# NixieModule_IN12.net
KiCad netlist of a schematic drawn in EAGLE
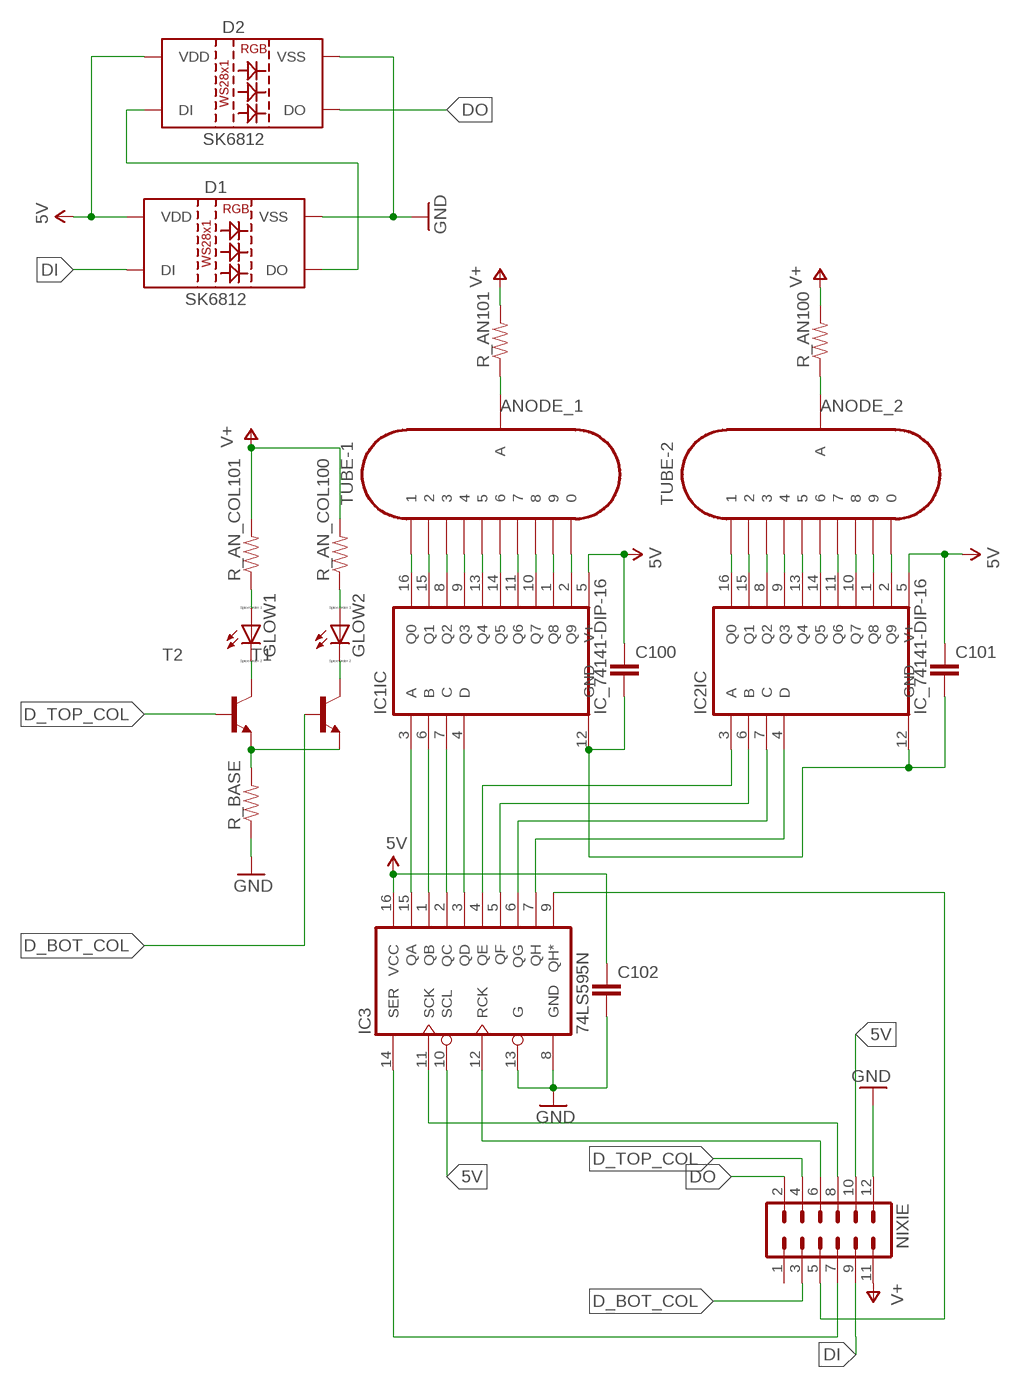
[diagram p0: schematic, sheet 1]

(export (version "E")
  (design (tool "Eeschema 10.0.6"))
  (components
    (comp (ref "C100")
      (value "C-EU050-024X044")
      (footprint "eagle-import:C050-024X044")
      (libsource (lib "eagle-import") (part "C-EU050-024X044"))
    )
    (comp (ref "C101")
      (value "C-EU050-024X044")
      (footprint "eagle-import:C050-024X044")
      (libsource (lib "eagle-import") (part "C-EU050-024X044"))
    )
    (comp (ref "C102")
      (value "C-EU050-024X044")
      (footprint "eagle-import:C050-024X044")
      (libsource (lib "eagle-import") (part "C-EU050-024X044"))
    )
    (comp (ref "D1")
      (value "SK6812")
      (footprint "eagle-import:WS2812B")
      (libsource (lib "eagle-import") (part "WS2812B"))
    )
    (comp (ref "D2")
      (value "SK6812")
      (footprint "eagle-import:WS2812B")
      (libsource (lib "eagle-import") (part "WS2812B"))
    )
    (comp (ref "GLOW1")
      (value "LED_ELD260")
      (footprint "eagle-import:LED_LD260")
      (libsource (lib "eagle-import") (part "LED_ELD260"))
    )
    (comp (ref "GLOW2")
      (value "LED_ELD260")
      (footprint "eagle-import:LED_LD260")
      (libsource (lib "eagle-import") (part "LED_ELD260"))
    )
    (comp (ref "IC1")
      (value "IC_74141-DIP-16")
      (footprint "eagle-import:DIL16")
      (libsource (lib "eagle-import") (part "IC_74141-DIP-16"))
    )
    (comp (ref "IC2")
      (value "IC_74141-DIP-16")
      (footprint "eagle-import:DIL16")
      (libsource (lib "eagle-import") (part "IC_74141-DIP-16"))
    )
    (comp (ref "IC3")
      (value "74LS595N")
      (footprint "eagle-import:DIL16")
      (libsource (lib "eagle-import") (part "74595NLS"))
    )
    (comp (ref "NIXIE")
      (value "MA06-2")
      (footprint "eagle-import:MA06-2")
      (libsource (lib "eagle-import") (part "MA06-2"))
    )
    (comp (ref "R_AN100")
      (value "RESISTORPTH-1/4W")
      (footprint "eagle-import:AXIAL-0.4")
      (libsource (lib "eagle-import") (part "RESISTORPTH-1/4W"))
    )
    (comp (ref "R_AN101")
      (value "RESISTORPTH-1/4W")
      (footprint "eagle-import:AXIAL-0.4")
      (libsource (lib "eagle-import") (part "RESISTORPTH-1/4W"))
    )
    (comp (ref "R_AN_COL100")
      (value "RESISTORPTH-1/4W")
      (footprint "eagle-import:AXIAL-0.4")
      (libsource (lib "eagle-import") (part "RESISTORPTH-1/4W"))
    )
    (comp (ref "R_AN_COL101")
      (value "RESISTORPTH-1/4W")
      (footprint "eagle-import:AXIAL-0.4")
      (libsource (lib "eagle-import") (part "RESISTORPTH-1/4W"))
    )
    (comp (ref "R_BASE")
      (value "RESISTORPTH-1/4W")
      (footprint "eagle-import:AXIAL-0.4")
      (libsource (lib "eagle-import") (part "RESISTORPTH-1/4W"))
    )
    (comp (ref "T1")
      (value "-NPN-TO92-EBC")
      (footprint "eagle-import:TO92-EBC")
      (libsource (lib "eagle-import") (part "-NPN-TO92-EBC"))
    )
    (comp (ref "T2")
      (value "-NPN-TO92-EBC")
      (footprint "eagle-import:TO92-EBC")
      (libsource (lib "eagle-import") (part "-NPN-TO92-EBC"))
    )
    (comp (ref "TUBE-1")
      (value "IN-12A")
      (footprint "eagle-import:IN-12")
      (libsource (lib "eagle-import") (part "IN-12A"))
    )
    (comp (ref "TUBE-2")
      (value "IN-12A")
      (footprint "eagle-import:IN-12")
      (libsource (lib "eagle-import") (part "IN-12A"))
    )
  )
  (nets
    (net (code "1") (name "/ANODE_1") (class "Default")
      (node (ref "R_AN101") (pin "P$1") (pinfunction "1_P$1") (pintype "passive"))
      (node (ref "TUBE-1") (pin "A") (pinfunction "A_A") (pintype "bidirectional"))
    )
    (net (code "2") (name "/ANODE_2") (class "Default")
      (node (ref "R_AN100") (pin "P$1") (pinfunction "1_P$1") (pintype "passive"))
      (node (ref "TUBE-2") (pin "A") (pinfunction "A_A") (pintype "bidirectional"))
    )
    (net (code "3") (name "5V") (class "Default")
      (node (ref "C100") (pin "1") (pinfunction "1_1") (pintype "passive"))
      (node (ref "C101") (pin "1") (pinfunction "1_1") (pintype "passive"))
      (node (ref "C102") (pin "1") (pinfunction "1_1") (pintype "passive"))
      (node (ref "D1") (pin "1") (pinfunction "VDD_1") (pintype "bidirectional"))
      (node (ref "D2") (pin "1") (pinfunction "VDD_1") (pintype "bidirectional"))
      (node (ref "IC1") (pin "5") (pinfunction "V+_5") (pintype "power_in"))
      (node (ref "IC2") (pin "5") (pinfunction "V+_5") (pintype "power_in"))
      (node (ref "IC3") (pin "10") (pinfunction "SCL_10") (pintype "input"))
      (node (ref "IC3") (pin "16") (pinfunction "VCC_16") (pintype "power_in"))
      (node (ref "NIXIE") (pin "10") (pinfunction "10_10") (pintype "passive"))
    )
    (net (code "4") (name "DI") (class "Default")
      (node (ref "D1") (pin "4") (pinfunction "DI_4") (pintype "bidirectional"))
      (node (ref "NIXIE") (pin "9") (pinfunction "9_9") (pintype "passive"))
    )
    (net (code "5") (name "DO") (class "Default")
      (node (ref "D2") (pin "2") (pinfunction "DO_2") (pintype "bidirectional"))
      (node (ref "NIXIE") (pin "2") (pinfunction "2_2") (pintype "passive"))
    )
    (net (code "6") (name "D_BOT_COL") (class "Default")
      (node (ref "NIXIE") (pin "3") (pinfunction "3_3") (pintype "passive"))
      (node (ref "T1") (pin "B") (pinfunction "B_B") (pintype "passive"))
    )
    (net (code "7") (name "D_TOP_COL") (class "Default")
      (node (ref "NIXIE") (pin "4") (pinfunction "4_4") (pintype "passive"))
      (node (ref "T2") (pin "B") (pinfunction "B_B") (pintype "passive"))
    )
    (net (code "8") (name "GND") (class "Default")
      (node (ref "C100") (pin "2") (pinfunction "2_2") (pintype "passive"))
      (node (ref "C101") (pin "2") (pinfunction "2_2") (pintype "passive"))
      (node (ref "C102") (pin "2") (pinfunction "2_2") (pintype "passive"))
      (node (ref "D1") (pin "3") (pinfunction "VSS_3") (pintype "bidirectional"))
      (node (ref "D2") (pin "3") (pinfunction "VSS_3") (pintype "bidirectional"))
      (node (ref "IC1") (pin "12") (pinfunction "GND_12") (pintype "power_in"))
      (node (ref "IC2") (pin "12") (pinfunction "GND_12") (pintype "power_in"))
      (node (ref "IC3") (pin "13") (pinfunction "G_13") (pintype "input"))
      (node (ref "IC3") (pin "8") (pinfunction "GND_8") (pintype "power_in"))
      (node (ref "NIXIE") (pin "12") (pinfunction "12_12") (pintype "passive"))
      (node (ref "R_BASE") (pin "P$1") (pinfunction "1_P$1") (pintype "passive"))
    )
    (net (code "9") (name "Net-(D1-DO)") (class "Default")
      (node (ref "D1") (pin "2") (pinfunction "DO_2") (pintype "bidirectional"))
      (node (ref "D2") (pin "4") (pinfunction "DI_4") (pintype "bidirectional"))
    )
    (net (code "10") (name "Net-(GLOW1-C)") (class "Default")
      (node (ref "GLOW1") (pin "K") (pinfunction "C_K") (pintype "passive"))
      (node (ref "T2") (pin "C") (pinfunction "C_C") (pintype "passive"))
    )
    (net (code "11") (name "Net-(GLOW2-C)") (class "Default")
      (node (ref "GLOW2") (pin "K") (pinfunction "C_K") (pintype "passive"))
      (node (ref "T1") (pin "C") (pinfunction "C_C") (pintype "passive"))
    )
    (net (code "12") (name "Net-(IC1A-A)") (class "Default")
      (node (ref "IC1") (pin "3") (pinfunction "A_3") (pintype "input"))
      (node (ref "IC3") (pin "15") (pinfunction "QA_15") (pintype "tri_state"))
    )
    (net (code "13") (name "Net-(IC1A-B)") (class "Default")
      (node (ref "IC1") (pin "6") (pinfunction "B_6") (pintype "input"))
      (node (ref "IC3") (pin "1") (pinfunction "QB_1") (pintype "tri_state"))
    )
    (net (code "14") (name "Net-(IC1A-C)") (class "Default")
      (node (ref "IC1") (pin "7") (pinfunction "C_7") (pintype "input"))
      (node (ref "IC3") (pin "2") (pinfunction "QC_2") (pintype "tri_state"))
    )
    (net (code "15") (name "Net-(IC1A-D)") (class "Default")
      (node (ref "IC1") (pin "4") (pinfunction "D_4") (pintype "input"))
      (node (ref "IC3") (pin "3") (pinfunction "QD_3") (pintype "tri_state"))
    )
    (net (code "16") (name "Net-(IC1A-Q0)") (class "Default")
      (node (ref "IC1") (pin "16") (pinfunction "Q0_16") (pintype "output"))
      (node (ref "TUBE-1") (pin "1") (pinfunction "1_1") (pintype "bidirectional"))
    )
    (net (code "17") (name "Net-(IC1A-Q1)") (class "Default")
      (node (ref "IC1") (pin "15") (pinfunction "Q1_15") (pintype "output"))
      (node (ref "TUBE-1") (pin "2") (pinfunction "2_2") (pintype "bidirectional"))
    )
    (net (code "18") (name "Net-(IC1A-Q2)") (class "Default")
      (node (ref "IC1") (pin "8") (pinfunction "Q2_8") (pintype "output"))
      (node (ref "TUBE-1") (pin "3") (pinfunction "3_3") (pintype "bidirectional"))
    )
    (net (code "19") (name "Net-(IC1A-Q3)") (class "Default")
      (node (ref "IC1") (pin "9") (pinfunction "Q3_9") (pintype "output"))
      (node (ref "TUBE-1") (pin "4") (pinfunction "4_4") (pintype "bidirectional"))
    )
    (net (code "20") (name "Net-(IC1A-Q4)") (class "Default")
      (node (ref "IC1") (pin "13") (pinfunction "Q4_13") (pintype "output"))
      (node (ref "TUBE-1") (pin "5") (pinfunction "5_5") (pintype "bidirectional"))
    )
    (net (code "21") (name "Net-(IC1A-Q5)") (class "Default")
      (node (ref "IC1") (pin "14") (pinfunction "Q5_14") (pintype "output"))
      (node (ref "TUBE-1") (pin "6") (pinfunction "6_6") (pintype "bidirectional"))
    )
    (net (code "22") (name "Net-(IC1A-Q6)") (class "Default")
      (node (ref "IC1") (pin "11") (pinfunction "Q6_11") (pintype "output"))
      (node (ref "TUBE-1") (pin "7") (pinfunction "7_7") (pintype "bidirectional"))
    )
    (net (code "23") (name "Net-(IC1A-Q7)") (class "Default")
      (node (ref "IC1") (pin "10") (pinfunction "Q7_10") (pintype "output"))
      (node (ref "TUBE-1") (pin "8") (pinfunction "8_8") (pintype "bidirectional"))
    )
    (net (code "24") (name "Net-(IC1A-Q8)") (class "Default")
      (node (ref "IC1") (pin "1") (pinfunction "Q8_1") (pintype "output"))
      (node (ref "TUBE-1") (pin "9") (pinfunction "9_9") (pintype "bidirectional"))
    )
    (net (code "25") (name "Net-(IC1A-Q9)") (class "Default")
      (node (ref "IC1") (pin "2") (pinfunction "Q9_2") (pintype "output"))
      (node (ref "TUBE-1") (pin "0") (pinfunction "0_0") (pintype "bidirectional"))
    )
    (net (code "26") (name "Net-(IC2A-A)") (class "Default")
      (node (ref "IC2") (pin "3") (pinfunction "A_3") (pintype "input"))
      (node (ref "IC3") (pin "4") (pinfunction "QE_4") (pintype "tri_state"))
    )
    (net (code "27") (name "Net-(IC2A-B)") (class "Default")
      (node (ref "IC2") (pin "6") (pinfunction "B_6") (pintype "input"))
      (node (ref "IC3") (pin "5") (pinfunction "QF_5") (pintype "tri_state"))
    )
    (net (code "28") (name "Net-(IC2A-C)") (class "Default")
      (node (ref "IC2") (pin "7") (pinfunction "C_7") (pintype "input"))
      (node (ref "IC3") (pin "6") (pinfunction "QG_6") (pintype "tri_state"))
    )
    (net (code "29") (name "Net-(IC2A-D)") (class "Default")
      (node (ref "IC2") (pin "4") (pinfunction "D_4") (pintype "input"))
      (node (ref "IC3") (pin "7") (pinfunction "QH_7") (pintype "tri_state"))
    )
    (net (code "30") (name "Net-(IC2A-Q0)") (class "Default")
      (node (ref "IC2") (pin "16") (pinfunction "Q0_16") (pintype "output"))
      (node (ref "TUBE-2") (pin "1") (pinfunction "1_1") (pintype "bidirectional"))
    )
    (net (code "31") (name "Net-(IC2A-Q1)") (class "Default")
      (node (ref "IC2") (pin "15") (pinfunction "Q1_15") (pintype "output"))
      (node (ref "TUBE-2") (pin "2") (pinfunction "2_2") (pintype "bidirectional"))
    )
    (net (code "32") (name "Net-(IC2A-Q2)") (class "Default")
      (node (ref "IC2") (pin "8") (pinfunction "Q2_8") (pintype "output"))
      (node (ref "TUBE-2") (pin "3") (pinfunction "3_3") (pintype "bidirectional"))
    )
    (net (code "33") (name "Net-(IC2A-Q3)") (class "Default")
      (node (ref "IC2") (pin "9") (pinfunction "Q3_9") (pintype "output"))
      (node (ref "TUBE-2") (pin "4") (pinfunction "4_4") (pintype "bidirectional"))
    )
    (net (code "34") (name "Net-(IC2A-Q4)") (class "Default")
      (node (ref "IC2") (pin "13") (pinfunction "Q4_13") (pintype "output"))
      (node (ref "TUBE-2") (pin "5") (pinfunction "5_5") (pintype "bidirectional"))
    )
    (net (code "35") (name "Net-(IC2A-Q5)") (class "Default")
      (node (ref "IC2") (pin "14") (pinfunction "Q5_14") (pintype "output"))
      (node (ref "TUBE-2") (pin "6") (pinfunction "6_6") (pintype "bidirectional"))
    )
    (net (code "36") (name "Net-(IC2A-Q6)") (class "Default")
      (node (ref "IC2") (pin "11") (pinfunction "Q6_11") (pintype "output"))
      (node (ref "TUBE-2") (pin "7") (pinfunction "7_7") (pintype "bidirectional"))
    )
    (net (code "37") (name "Net-(IC2A-Q7)") (class "Default")
      (node (ref "IC2") (pin "10") (pinfunction "Q7_10") (pintype "output"))
      (node (ref "TUBE-2") (pin "8") (pinfunction "8_8") (pintype "bidirectional"))
    )
    (net (code "38") (name "Net-(IC2A-Q8)") (class "Default")
      (node (ref "IC2") (pin "1") (pinfunction "Q8_1") (pintype "output"))
      (node (ref "TUBE-2") (pin "9") (pinfunction "9_9") (pintype "bidirectional"))
    )
    (net (code "39") (name "Net-(IC2A-Q9)") (class "Default")
      (node (ref "IC2") (pin "2") (pinfunction "Q9_2") (pintype "output"))
      (node (ref "TUBE-2") (pin "0") (pinfunction "0_0") (pintype "bidirectional"))
    )
    (net (code "40") (name "Net-(IC3-QH*)") (class "Default")
      (node (ref "IC3") (pin "9") (pinfunction "QH*_9") (pintype "tri_state"))
      (node (ref "NIXIE") (pin "5") (pinfunction "5_5") (pintype "passive"))
    )
    (net (code "41") (name "Net-(IC3-RCK)") (class "Default")
      (node (ref "IC3") (pin "12") (pinfunction "RCK_12") (pintype "input"))
      (node (ref "NIXIE") (pin "6") (pinfunction "6_6") (pintype "passive"))
    )
    (net (code "42") (name "Net-(IC3-SCK)") (class "Default")
      (node (ref "IC3") (pin "11") (pinfunction "SCK_11") (pintype "input"))
      (node (ref "NIXIE") (pin "8") (pinfunction "8_8") (pintype "passive"))
    )
    (net (code "43") (name "Net-(IC3-SER)") (class "Default")
      (node (ref "IC3") (pin "14") (pinfunction "SER_14") (pintype "input"))
      (node (ref "NIXIE") (pin "7") (pinfunction "7_7") (pintype "passive"))
    )
    (net (code "44") (name "Net-(R_AN_COL100-1)") (class "Default")
      (node (ref "GLOW2") (pin "A") (pinfunction "A_A") (pintype "passive"))
      (node (ref "R_AN_COL100") (pin "P$1") (pinfunction "1_P$1") (pintype "passive"))
    )
    (net (code "45") (name "Net-(R_AN_COL101-1)") (class "Default")
      (node (ref "GLOW1") (pin "A") (pinfunction "A_A") (pintype "passive"))
      (node (ref "R_AN_COL101") (pin "P$1") (pinfunction "1_P$1") (pintype "passive"))
    )
    (net (code "46") (name "Net-(R_BASE-2)") (class "Default")
      (node (ref "R_BASE") (pin "P$2") (pinfunction "2_P$2") (pintype "passive"))
      (node (ref "T1") (pin "E") (pinfunction "E_E") (pintype "passive"))
      (node (ref "T2") (pin "E") (pinfunction "E_E") (pintype "passive"))
    )
    (net (code "47") (name "V+") (class "Default")
      (node (ref "NIXIE") (pin "11") (pinfunction "11_11") (pintype "passive"))
      (node (ref "R_AN100") (pin "P$2") (pinfunction "2_P$2") (pintype "passive"))
      (node (ref "R_AN101") (pin "P$2") (pinfunction "2_P$2") (pintype "passive"))
      (node (ref "R_AN_COL100") (pin "P$2") (pinfunction "2_P$2") (pintype "passive"))
      (node (ref "R_AN_COL101") (pin "P$2") (pinfunction "2_P$2") (pintype "passive"))
    )
    (net (code "48") (name "unconnected-(NIXIE-Pad1)") (class "Default")
      (node (ref "NIXIE") (pin "1") (pinfunction "1_1") (pintype "passive"))
    )
  )
)
